# nerves_key4.net
KiCad netlist of a schematic drawn in EAGLE
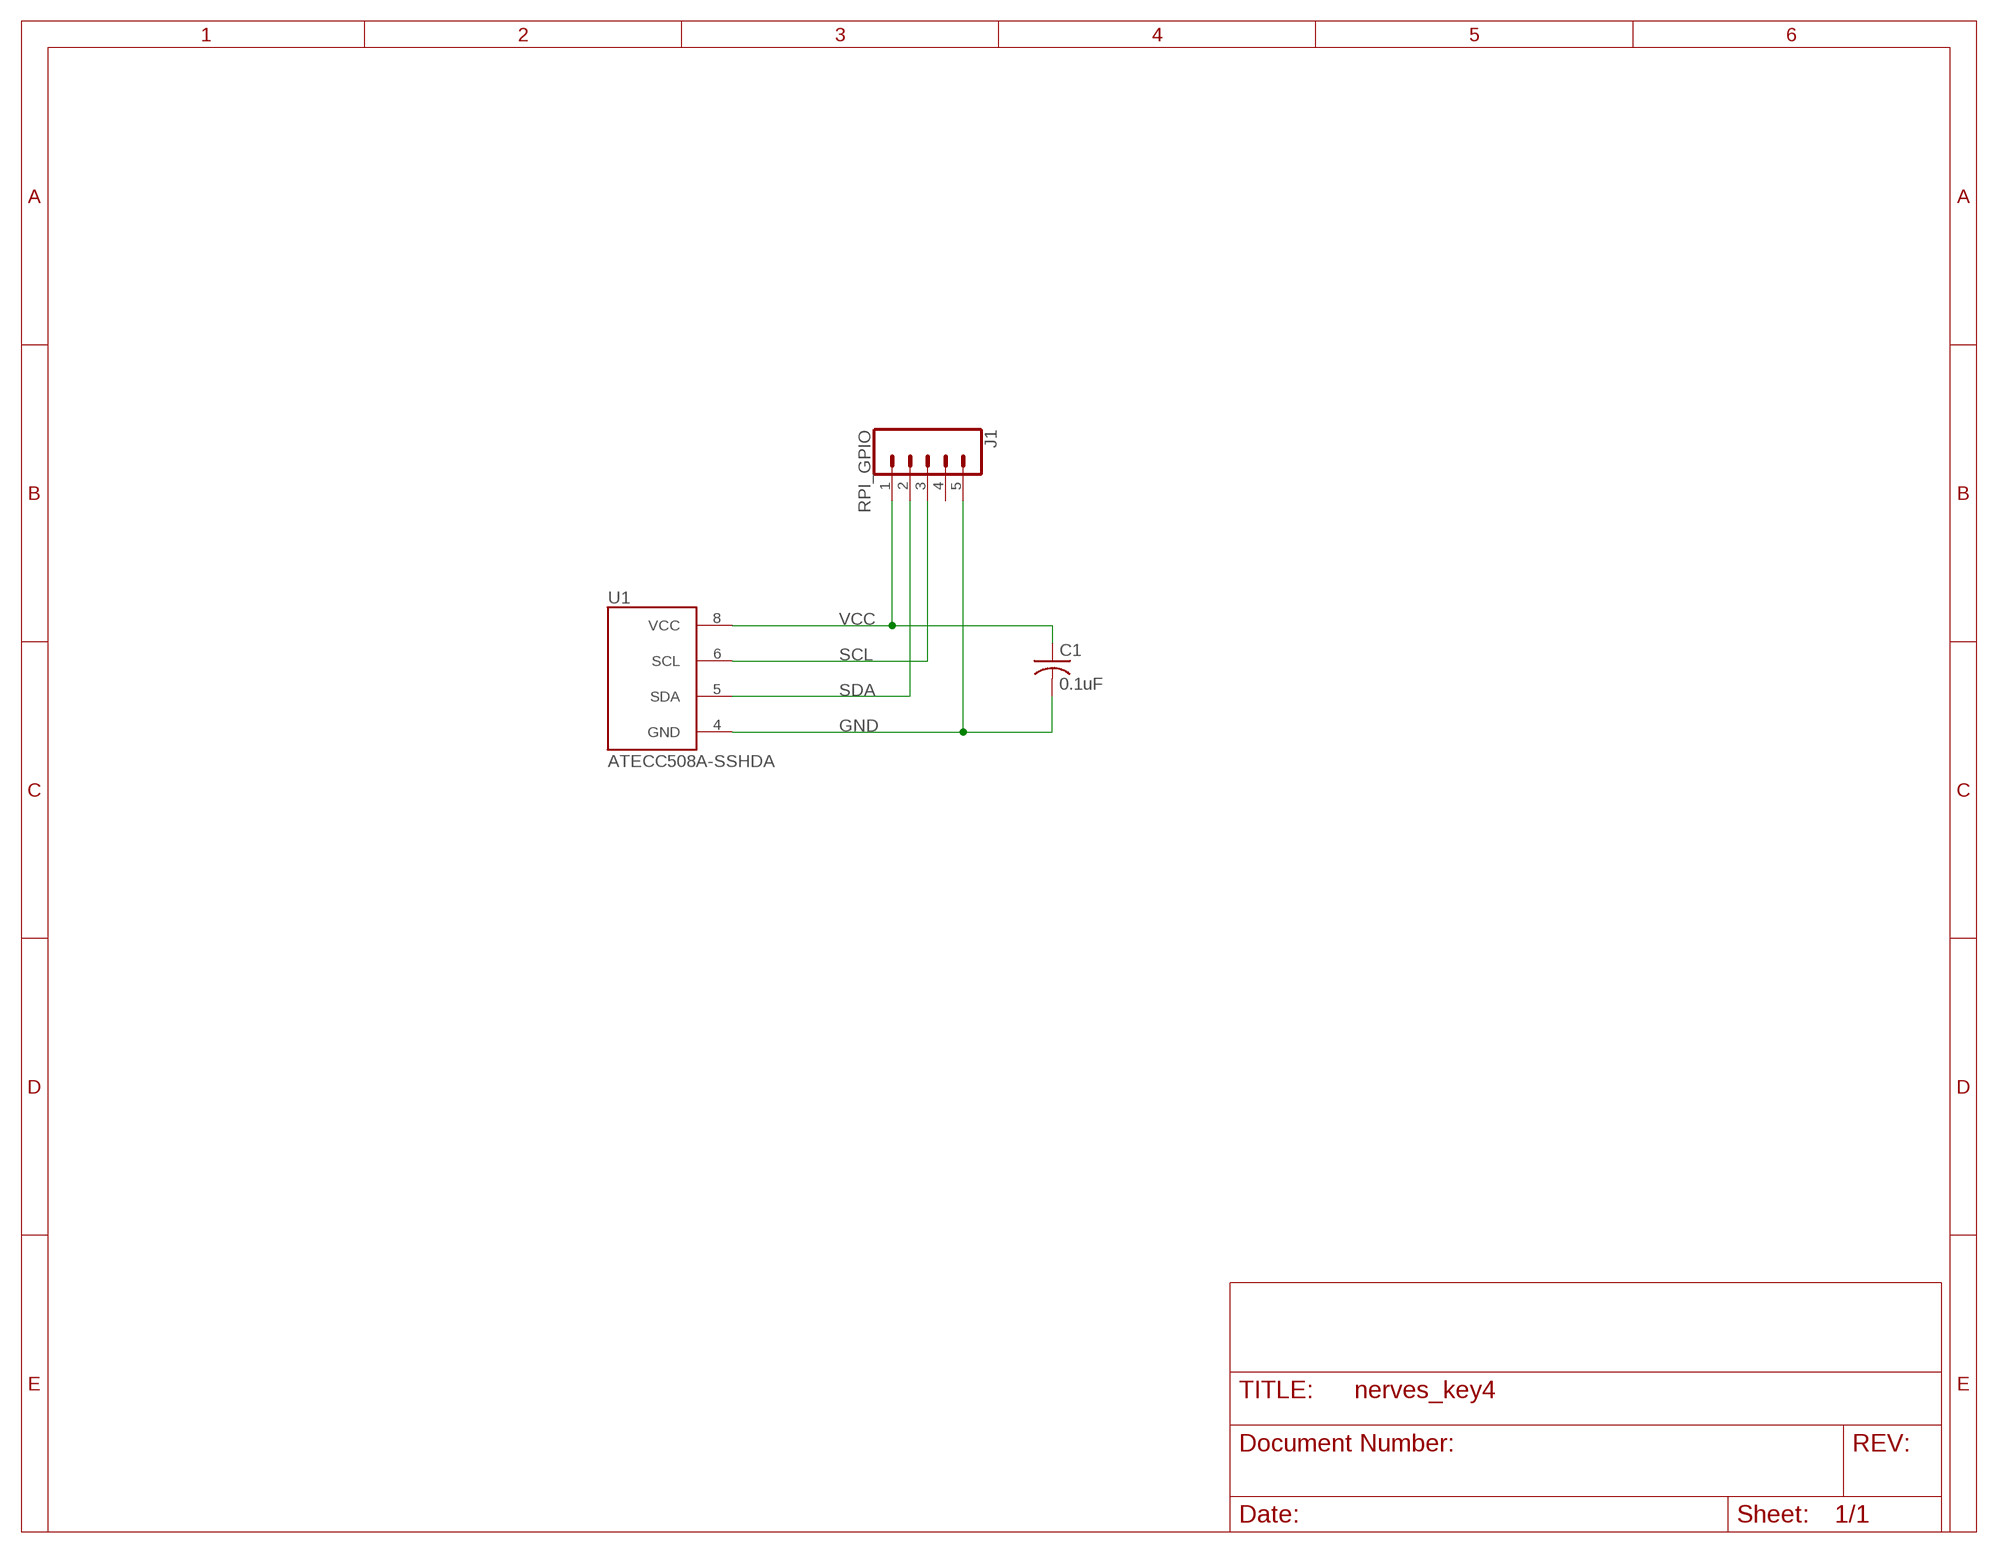
[diagram p0: schematic, sheet 1]

(export (version "E")
  (design (tool "Eeschema 10.0.6"))
  (components
    (comp (ref "C1")
      (value "0.1uF")
      (footprint "eagle-import:C0603")
      (libsource (lib "eagle-import") (part "C-USC0603"))
    )
    (comp (ref "J1")
      (value "RPI_GPIO")
      (footprint "eagle-import:1X05")
      (libsource (lib "eagle-import") (part "CONN_05"))
    )
    (comp (ref "U1")
      (value "ATECC508A-SSHDA")
      (footprint "eagle-import:SOIC127P625X175-8")
      (libsource (lib "eagle-import") (part "ATECC508ASOIC-8-NARROW"))
    )
  )
  (nets
    (net (code "1") (name "/GND") (class "Default")
      (node (ref "C1") (pin "2") (pinfunction "2_2") (pintype "passive"))
      (node (ref "J1") (pin "5") (pinfunction "5_5") (pintype "passive"))
      (node (ref "U1") (pin "4") (pinfunction "GND_4") (pintype "bidirectional"))
    )
    (net (code "2") (name "/SCL") (class "Default")
      (node (ref "J1") (pin "3") (pinfunction "3_3") (pintype "passive"))
      (node (ref "U1") (pin "6") (pinfunction "SCL_6") (pintype "bidirectional"))
    )
    (net (code "3") (name "/SDA") (class "Default")
      (node (ref "J1") (pin "2") (pinfunction "2_2") (pintype "passive"))
      (node (ref "U1") (pin "5") (pinfunction "SDA_5") (pintype "bidirectional"))
    )
    (net (code "4") (name "/VCC") (class "Default")
      (node (ref "C1") (pin "1") (pinfunction "1_1") (pintype "passive"))
      (node (ref "J1") (pin "1") (pinfunction "1_1") (pintype "passive"))
      (node (ref "U1") (pin "8") (pinfunction "VCC_8") (pintype "bidirectional"))
    )
    (net (code "5") (name "unconnected-(J1-Pad4)") (class "Default")
      (node (ref "J1") (pin "4") (pinfunction "4_4") (pintype "passive"))
    )
  )
)
